# SmartRockMS5803.net
KiCad netlist of a schematic drawn in EAGLE
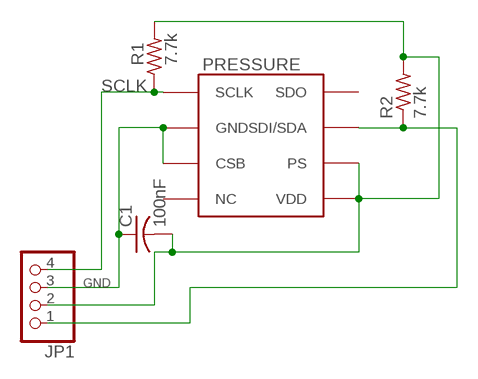
[diagram p0: schematic, sheet 1]

(export (version "E")
  (design (tool "Eeschema 10.0.6"))
  (components
    (comp (ref "C1")
      (value "100nF")
      (footprint "eagle-import:C0805")
      (libsource (lib "eagle-import") (part "C-USC0805"))
    )
    (comp (ref "JP1")
      (value "PINHD-1X4")
      (footprint "eagle-import:1X04")
      (libsource (lib "eagle-import") (part "PINHD-1X4"))
    )
    (comp (ref "PRESSURE")
      (value "MS5803-01BA")
      (footprint "eagle-import:SMD")
      (libsource (lib "eagle-import") (part "MS5803-01BA"))
    )
    (comp (ref "R1")
      (value "7.7k")
      (footprint "eagle-import:R0805")
      (libsource (lib "eagle-import") (part "R-US_R0805"))
    )
    (comp (ref "R2")
      (value "7.7k")
      (footprint "eagle-import:R0805")
      (libsource (lib "eagle-import") (part "R-US_R0805"))
    )
  )
  (nets
    (net (code "1") (name "/GND") (class "Default")
      (node (ref "C1") (pin "1") (pinfunction "1_1") (pintype "passive"))
      (node (ref "JP1") (pin "3") (pinfunction "3_3") (pintype "passive"))
      (node (ref "PRESSURE") (pin "CSB") (pinfunction "CSB_CSB") (pintype "bidirectional"))
      (node (ref "PRESSURE") (pin "GND") (pinfunction "GND_GND") (pintype "bidirectional"))
    )
    (net (code "2") (name "/SCLK") (class "Default")
      (node (ref "JP1") (pin "4") (pinfunction "4_4") (pintype "passive"))
      (node (ref "PRESSURE") (pin "SCLK") (pinfunction "SCLK_SCLK") (pintype "bidirectional"))
      (node (ref "R1") (pin "1") (pinfunction "1_1") (pintype "passive"))
    )
    (net (code "3") (name "Net-(C1-Pad2)") (class "Default")
      (node (ref "C1") (pin "2") (pinfunction "2_2") (pintype "passive"))
      (node (ref "JP1") (pin "2") (pinfunction "2_2") (pintype "passive"))
      (node (ref "PRESSURE") (pin "PS") (pinfunction "PS_PS") (pintype "bidirectional"))
      (node (ref "PRESSURE") (pin "VDD") (pinfunction "VDD_VDD") (pintype "bidirectional"))
      (node (ref "R1") (pin "2") (pinfunction "2_2") (pintype "passive"))
      (node (ref "R2") (pin "2") (pinfunction "2_2") (pintype "passive"))
    )
    (net (code "4") (name "Net-(JP1-Pad1)") (class "Default")
      (node (ref "JP1") (pin "1") (pinfunction "1_1") (pintype "passive"))
      (node (ref "PRESSURE") (pin "SDI/SDA") (pinfunction "SDI/SDA_SDI/SDA") (pintype "bidirectional"))
      (node (ref "R2") (pin "1") (pinfunction "1_1") (pintype "passive"))
    )
    (net (code "5") (name "unconnected-(PRESSURE-PadNC)") (class "Default")
      (node (ref "PRESSURE") (pin "NC") (pinfunction "NC_NC") (pintype "bidirectional"))
    )
    (net (code "6") (name "unconnected-(PRESSURE-PadSDO)") (class "Default")
      (node (ref "PRESSURE") (pin "SDO") (pinfunction "SDO_SDO") (pintype "bidirectional"))
    )
  )
)
